# Wireach_internal_Buffered.net
KiCad netlist of a schematic drawn in EAGLE
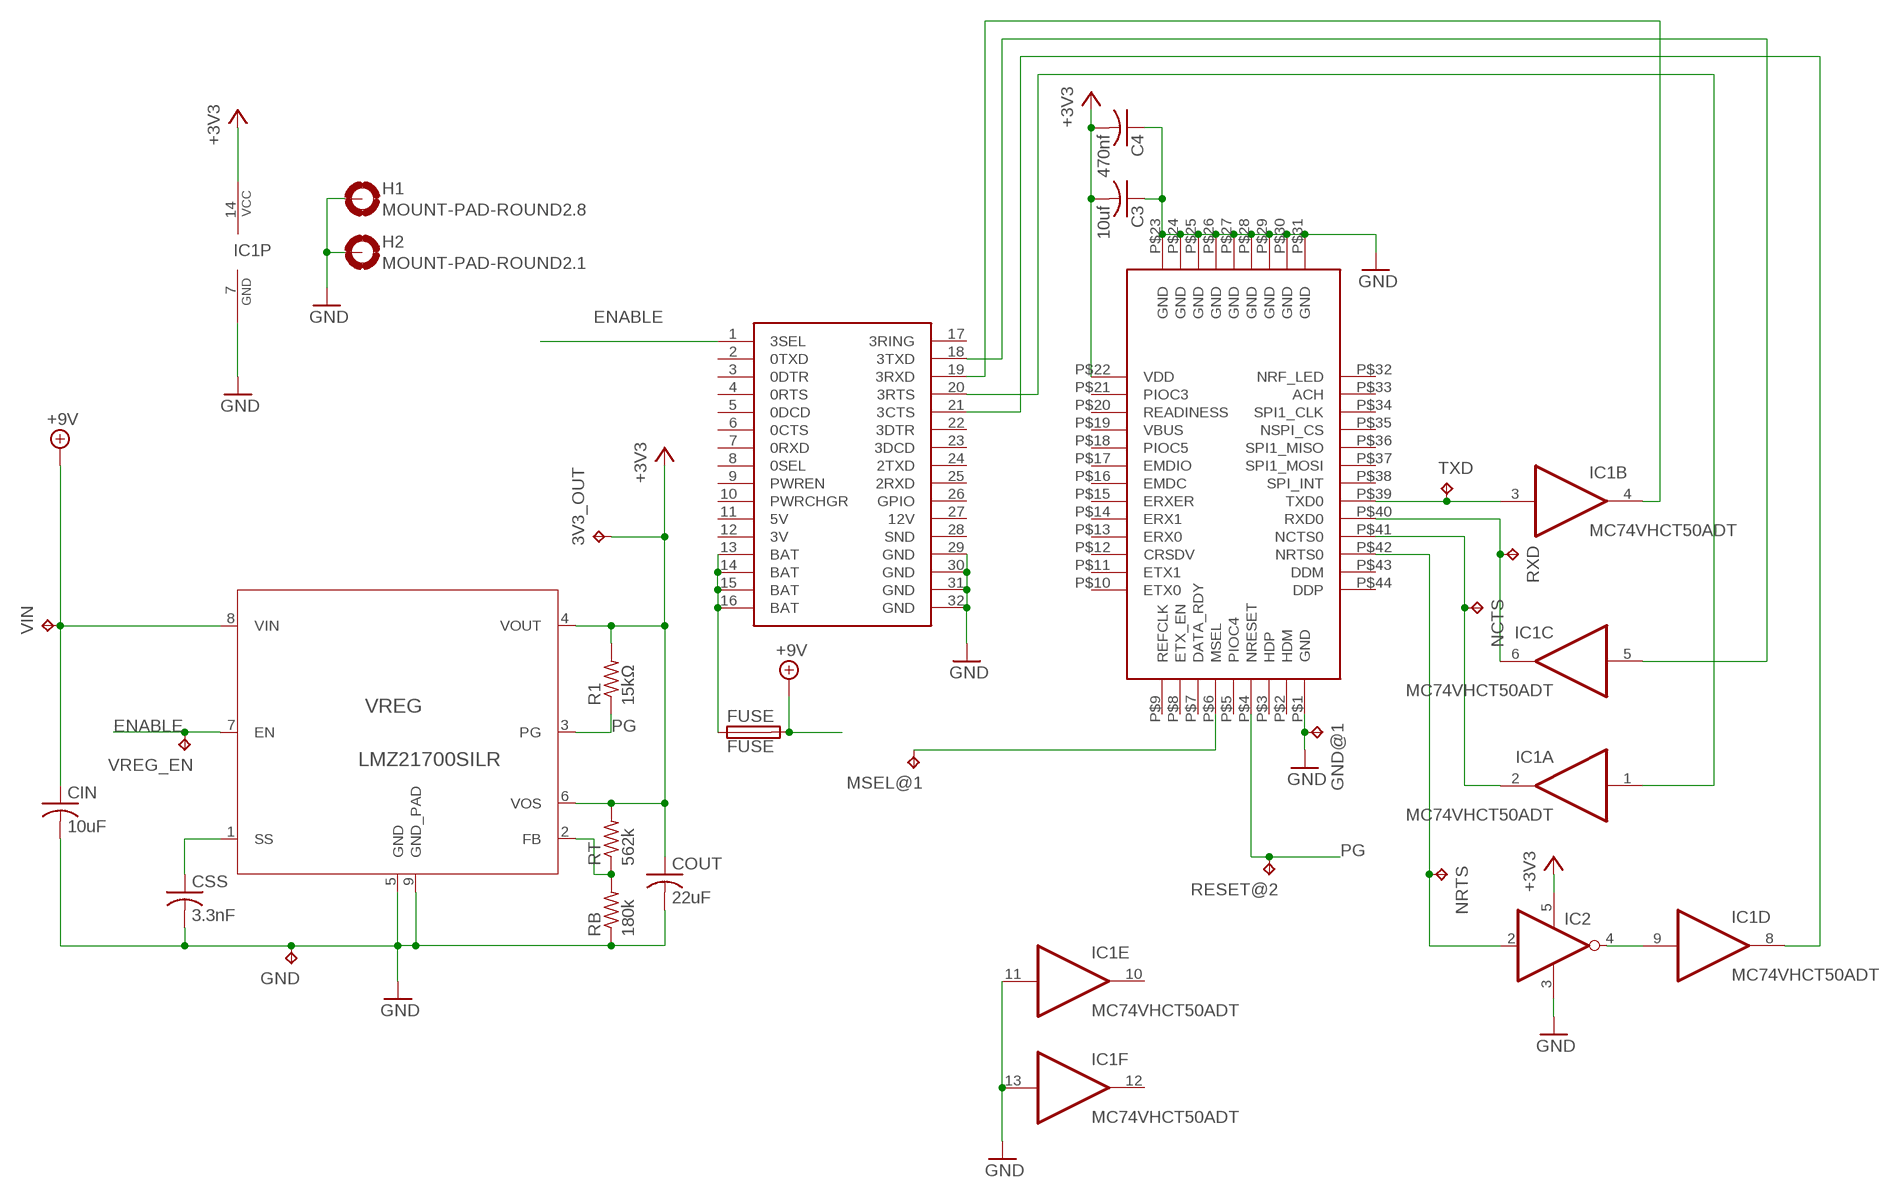
[diagram p0: schematic, sheet 1]

(export (version "E")
  (design (tool "Eeschema 10.0.6"))
  (components
    (comp (ref "3V3_OUT")
      (value "TPTP10R")
      (footprint "eagle-import:TP10R")
      (libsource (lib "eagle-import") (part "TPTP10R"))
    )
    (comp (ref "C3")
      (value "10uf")
      (footprint "eagle-import:C0805")
      (libsource (lib "eagle-import") (part "C-USC0805"))
    )
    (comp (ref "C4")
      (value "470nf")
      (footprint "eagle-import:C0805")
      (libsource (lib "eagle-import") (part "C-USC0805"))
    )
    (comp (ref "CIN")
      (value "10uF")
      (footprint "eagle-import:C0805K")
      (libsource (lib "eagle-import") (part "C-USC0805K"))
    )
    (comp (ref "COUT")
      (value "22uF")
      (footprint "eagle-import:C0805K")
      (libsource (lib "eagle-import") (part "C-USC0805K"))
    )
    (comp (ref "CSS")
      (value "3.3nF")
      (footprint "eagle-import:C0603K")
      (libsource (lib "eagle-import") (part "C-USC0603K"))
    )
    (comp (ref "FUSE")
      (value "FUSE")
      (footprint "eagle-import:R1206")
      (libsource (lib "eagle-import") (part "FUSE"))
    )
    (comp (ref "GND")
      (value "TPTP10R")
      (footprint "eagle-import:TP10R")
      (libsource (lib "eagle-import") (part "TPTP10R"))
    )
    (comp (ref "GND@1")
      (value "TPTP10R")
      (footprint "eagle-import:TP10R")
      (libsource (lib "eagle-import") (part "TPTP10R"))
    )
    (comp (ref "H1")
      (value "MOUNT-PAD-ROUND2.8")
      (footprint "eagle-import:2,8-PAD")
      (libsource (lib "eagle-import") (part "MOUNT-PAD-ROUND2.8"))
    )
    (comp (ref "H2")
      (value "MOUNT-PAD-ROUND2.1")
      (footprint "eagle-import:2,1-PAD")
      (libsource (lib "eagle-import") (part "MOUNT-PAD-ROUND2.1"))
    )
    (comp (ref "IC1")
      (value "MC74VHCT50ADT")
      (footprint "eagle-import:TSSOP14")
      (libsource (lib "eagle-import") (part "MC74VHCT50ADT"))
    )
    (comp (ref "IC2")
      (value "1G04-DC")
      (footprint "eagle-import:SOT353_5")
      (libsource (lib "eagle-import") (part "1G04-DC"))
    )
    (comp (ref "MSEL@1")
      (value "TPTP10R")
      (footprint "eagle-import:TP10R")
      (libsource (lib "eagle-import") (part "TPTP10R"))
    )
    (comp (ref "NCTS")
      (value "TPTP10R")
      (footprint "eagle-import:TP10R")
      (libsource (lib "eagle-import") (part "TPTP10R"))
    )
    (comp (ref "NRTS")
      (value "TPTP10R")
      (footprint "eagle-import:TP10R")
      (libsource (lib "eagle-import") (part "TPTP10R"))
    )
    (comp (ref "R1")
      (value "15kΩ")
      (footprint "eagle-import:R0603")
      (libsource (lib "eagle-import") (part "R-US_R0603"))
    )
    (comp (ref "RB")
      (value "180k")
      (footprint "eagle-import:R0603")
      (libsource (lib "eagle-import") (part "resistor_R-US_R0603"))
    )
    (comp (ref "RESET@2")
      (value "TPTP10R")
      (footprint "eagle-import:TP10R")
      (libsource (lib "eagle-import") (part "TPTP10R"))
    )
    (comp (ref "RT")
      (value "562k")
      (footprint "eagle-import:R0603")
      (libsource (lib "eagle-import") (part "resistor_R-US_R0603"))
    )
    (comp (ref "RXD")
      (value "TPTP10R")
      (footprint "eagle-import:TP10R")
      (libsource (lib "eagle-import") (part "TPTP10R"))
    )
    (comp (ref "TXD")
      (value "TPTP10R")
      (footprint "eagle-import:TP10R")
      (libsource (lib "eagle-import") (part "TPTP10R"))
    )
    (comp (ref "U$1")
      (value "WIREACH")
      (footprint "eagle-import:WIREACH")
      (libsource (lib "eagle-import") (part "WIREACH"))
    )
    (comp (ref "U$3")
      (value "N2-INTOLD")
      (footprint "eagle-import:NEWTON")
      (libsource (lib "eagle-import") (part "N2-INTOLD"))
    )
    (comp (ref "VIN")
      (value "TPTP10R")
      (footprint "eagle-import:TP10R")
      (libsource (lib "eagle-import") (part "TPTP10R"))
    )
    (comp (ref "VREG")
      (value "LMZ21700SILR")
      (footprint "eagle-import:SIL0008B")
      (libsource (lib "eagle-import") (part "LMZ21700SILR"))
    )
    (comp (ref "VREG_EN")
      (value "TPTP10R")
      (footprint "eagle-import:TP10R")
      (libsource (lib "eagle-import") (part "TPTP10R"))
    )
  )
  (nets
    (net (code "1") (name "+3V3") (class "Default")
      (node (ref "3V3_OUT") (pin "TP") (pinfunction "TP_TP") (pintype "input"))
      (node (ref "C3") (pin "2") (pinfunction "2_2") (pintype "passive"))
      (node (ref "C4") (pin "2") (pinfunction "2_2") (pintype "passive"))
      (node (ref "COUT") (pin "1") (pinfunction "1_1") (pintype "passive"))
      (node (ref "IC1") (pin "14") (pinfunction "VCC_14") (pintype "power_in"))
      (node (ref "IC2") (pin "5") (pinfunction "VDD_5") (pintype "power_in"))
      (node (ref "R1") (pin "2") (pinfunction "2_2") (pintype "passive"))
      (node (ref "RT") (pin "2") (pinfunction "2_2") (pintype "passive"))
      (node (ref "U$1") (pin "P$22") (pinfunction "VDD_P$22") (pintype "bidirectional"))
      (node (ref "VREG") (pin "4") (pinfunction "VOUT_4") (pintype "passive"))
      (node (ref "VREG") (pin "6") (pinfunction "VOS_6") (pintype "passive"))
    )
    (net (code "2") (name "+9V") (class "Default")
      (node (ref "CIN") (pin "1") (pinfunction "1_1") (pintype "passive"))
      (node (ref "FUSE") (pin "2") (pinfunction "2_2") (pintype "passive"))
      (node (ref "VIN") (pin "TP") (pinfunction "TP_TP") (pintype "input"))
      (node (ref "VREG") (pin "8") (pinfunction "VIN_8") (pintype "passive"))
    )
    (net (code "3") (name "/ENABLE") (class "Default")
      (node (ref "U$3") (pin "1") (pinfunction "3SEL_1") (pintype "bidirectional"))
      (node (ref "VREG") (pin "7") (pinfunction "EN_7") (pintype "passive"))
      (node (ref "VREG_EN") (pin "TP") (pinfunction "TP_TP") (pintype "input"))
    )
    (net (code "4") (name "/PG") (class "Default")
      (node (ref "R1") (pin "1") (pinfunction "1_1") (pintype "passive"))
      (node (ref "RESET@2") (pin "TP") (pinfunction "TP_TP") (pintype "input"))
      (node (ref "U$1") (pin "P$4") (pinfunction "NRESET_P$4") (pintype "bidirectional"))
      (node (ref "VREG") (pin "3") (pinfunction "PG_3") (pintype "passive"))
    )
    (net (code "5") (name "GND") (class "Default")
      (node (ref "C3") (pin "1") (pinfunction "1_1") (pintype "passive"))
      (node (ref "C4") (pin "1") (pinfunction "1_1") (pintype "passive"))
      (node (ref "CIN") (pin "2") (pinfunction "2_2") (pintype "passive"))
      (node (ref "COUT") (pin "2") (pinfunction "2_2") (pintype "passive"))
      (node (ref "CSS") (pin "2") (pinfunction "2_2") (pintype "passive"))
      (node (ref "GND") (pin "TP") (pinfunction "TP_TP") (pintype "input"))
      (node (ref "GND@1") (pin "TP") (pinfunction "TP_TP") (pintype "input"))
      (node (ref "H1") (pin "B2,8") (pinfunction "MOUNT_B2,8") (pintype "passive"))
      (node (ref "H2") (pin "B2,8") (pinfunction "MOUNT_B2,8") (pintype "passive"))
      (node (ref "IC1") (pin "11") (pinfunction "I_11") (pintype "input"))
      (node (ref "IC1") (pin "13") (pinfunction "I_13") (pintype "input"))
      (node (ref "IC1") (pin "7") (pinfunction "GND_7") (pintype "power_in"))
      (node (ref "IC2") (pin "3") (pinfunction "GND_3") (pintype "power_in"))
      (node (ref "RB") (pin "1") (pinfunction "1_1") (pintype "passive"))
      (node (ref "U$1") (pin "P$1") (pinfunction "GND_P$1") (pintype "bidirectional"))
      (node (ref "U$1") (pin "P$23") (pinfunction "GND_P$23") (pintype "bidirectional"))
      (node (ref "U$1") (pin "P$24") (pinfunction "GND_P$24") (pintype "bidirectional"))
      (node (ref "U$1") (pin "P$25") (pinfunction "GND_P$25") (pintype "bidirectional"))
      (node (ref "U$1") (pin "P$26") (pinfunction "GND_P$26") (pintype "bidirectional"))
      (node (ref "U$1") (pin "P$27") (pinfunction "GND_P$27") (pintype "bidirectional"))
      (node (ref "U$1") (pin "P$28") (pinfunction "GND_P$28") (pintype "bidirectional"))
      (node (ref "U$1") (pin "P$29") (pinfunction "GND_P$29") (pintype "bidirectional"))
      (node (ref "U$1") (pin "P$30") (pinfunction "GND_P$30") (pintype "bidirectional"))
      (node (ref "U$1") (pin "P$31") (pinfunction "GND_P$31") (pintype "bidirectional"))
      (node (ref "U$3") (pin "29") (pinfunction "GND_29") (pintype "bidirectional"))
      (node (ref "U$3") (pin "30") (pinfunction "GND_30") (pintype "bidirectional"))
      (node (ref "U$3") (pin "31") (pinfunction "GND_31") (pintype "bidirectional"))
      (node (ref "U$3") (pin "32") (pinfunction "GND_32") (pintype "bidirectional"))
      (node (ref "VREG") (pin "5") (pinfunction "GND_5") (pintype "passive"))
      (node (ref "VREG") (pin "9") (pinfunction "GND_PAD_9") (pintype "passive"))
    )
    (net (code "6") (name "Net-(FUSE-Pad1)") (class "Default")
      (node (ref "FUSE") (pin "1") (pinfunction "1_1") (pintype "passive"))
      (node (ref "U$3") (pin "13") (pinfunction "BAT_13") (pintype "bidirectional"))
      (node (ref "U$3") (pin "14") (pinfunction "BAT_14") (pintype "bidirectional"))
      (node (ref "U$3") (pin "15") (pinfunction "BAT_15") (pintype "bidirectional"))
      (node (ref "U$3") (pin "16") (pinfunction "BAT_16") (pintype "bidirectional"))
    )
    (net (code "7") (name "Net-(IC1A-I)") (class "Default")
      (node (ref "IC1") (pin "1") (pinfunction "I_1") (pintype "input"))
      (node (ref "U$3") (pin "20") (pinfunction "3RTS_20") (pintype "bidirectional"))
    )
    (net (code "8") (name "Net-(IC1A-O)") (class "Default")
      (node (ref "IC1") (pin "2") (pinfunction "O_2") (pintype "open_collector"))
      (node (ref "NCTS") (pin "TP") (pinfunction "TP_TP") (pintype "input"))
      (node (ref "U$1") (pin "P$41") (pinfunction "NCTS0_P$41") (pintype "bidirectional"))
    )
    (net (code "9") (name "Net-(IC1B-I)") (class "Default")
      (node (ref "IC1") (pin "3") (pinfunction "I_3") (pintype "input"))
      (node (ref "TXD") (pin "TP") (pinfunction "TP_TP") (pintype "input"))
      (node (ref "U$1") (pin "P$39") (pinfunction "TXD0_P$39") (pintype "bidirectional"))
    )
    (net (code "10") (name "Net-(IC1B-O)") (class "Default")
      (node (ref "IC1") (pin "4") (pinfunction "O_4") (pintype "open_collector"))
      (node (ref "U$3") (pin "19") (pinfunction "3RXD_19") (pintype "bidirectional"))
    )
    (net (code "11") (name "Net-(IC1C-I)") (class "Default")
      (node (ref "IC1") (pin "5") (pinfunction "I_5") (pintype "input"))
      (node (ref "U$3") (pin "18") (pinfunction "3TXD_18") (pintype "bidirectional"))
    )
    (net (code "12") (name "Net-(IC1C-O)") (class "Default")
      (node (ref "IC1") (pin "6") (pinfunction "O_6") (pintype "open_collector"))
      (node (ref "RXD") (pin "TP") (pinfunction "TP_TP") (pintype "input"))
      (node (ref "U$1") (pin "P$40") (pinfunction "RXD0_P$40") (pintype "bidirectional"))
    )
    (net (code "13") (name "Net-(IC1D-I)") (class "Default")
      (node (ref "IC1") (pin "9") (pinfunction "I_9") (pintype "input"))
      (node (ref "IC2") (pin "4") (pinfunction "O_4") (pintype "output"))
    )
    (net (code "14") (name "Net-(IC1D-O)") (class "Default")
      (node (ref "IC1") (pin "8") (pinfunction "O_8") (pintype "open_collector"))
      (node (ref "U$3") (pin "21") (pinfunction "3CTS_21") (pintype "bidirectional"))
    )
    (net (code "15") (name "Net-(IC2-I)") (class "Default")
      (node (ref "IC2") (pin "2") (pinfunction "I_2") (pintype "input"))
      (node (ref "NRTS") (pin "TP") (pinfunction "TP_TP") (pintype "input"))
      (node (ref "U$1") (pin "P$42") (pinfunction "NRTS0_P$42") (pintype "bidirectional"))
    )
    (net (code "16") (name "Net-(U$1-MSEL)") (class "Default")
      (node (ref "MSEL@1") (pin "TP") (pinfunction "TP_TP") (pintype "input"))
      (node (ref "U$1") (pin "P$6") (pinfunction "MSEL_P$6") (pintype "bidirectional"))
    )
    (net (code "17") (name "Net-(VREG-FB)") (class "Default")
      (node (ref "RB") (pin "2") (pinfunction "2_2") (pintype "passive"))
      (node (ref "RT") (pin "1") (pinfunction "1_1") (pintype "passive"))
      (node (ref "VREG") (pin "2") (pinfunction "FB_2") (pintype "passive"))
    )
    (net (code "18") (name "Net-(VREG-SS)") (class "Default")
      (node (ref "CSS") (pin "1") (pinfunction "1_1") (pintype "passive"))
      (node (ref "VREG") (pin "1") (pinfunction "SS_1") (pintype "passive"))
    )
    (net (code "19") (name "unconnected-(IC1E-O-Pad10)") (class "Default")
      (node (ref "IC1") (pin "10") (pinfunction "O_10") (pintype "open_collector"))
    )
    (net (code "20") (name "unconnected-(IC1F-O-Pad12)") (class "Default")
      (node (ref "IC1") (pin "12") (pinfunction "O_12") (pintype "open_collector"))
    )
    (net (code "21") (name "unconnected-(U$1-ACH-PadP$33)") (class "Default")
      (node (ref "U$1") (pin "P$33") (pinfunction "ACH_P$33") (pintype "bidirectional"))
    )
    (net (code "22") (name "unconnected-(U$1-CRSDV-PadP$12)") (class "Default")
      (node (ref "U$1") (pin "P$12") (pinfunction "CRSDV_P$12") (pintype "bidirectional"))
    )
    (net (code "23") (name "unconnected-(U$1-DATA_RDY-PadP$7)") (class "Default")
      (node (ref "U$1") (pin "P$7") (pinfunction "DATA_RDY_P$7") (pintype "bidirectional"))
    )
    (net (code "24") (name "unconnected-(U$1-DDM-PadP$43)") (class "Default")
      (node (ref "U$1") (pin "P$43") (pinfunction "DDM_P$43") (pintype "bidirectional"))
    )
    (net (code "25") (name "unconnected-(U$1-DDP-PadP$44)") (class "Default")
      (node (ref "U$1") (pin "P$44") (pinfunction "DDP_P$44") (pintype "bidirectional"))
    )
    (net (code "26") (name "unconnected-(U$1-EMDC-PadP$16)") (class "Default")
      (node (ref "U$1") (pin "P$16") (pinfunction "EMDC_P$16") (pintype "bidirectional"))
    )
    (net (code "27") (name "unconnected-(U$1-EMDIO-PadP$17)") (class "Default")
      (node (ref "U$1") (pin "P$17") (pinfunction "EMDIO_P$17") (pintype "bidirectional"))
    )
    (net (code "28") (name "unconnected-(U$1-ERX0-PadP$13)") (class "Default")
      (node (ref "U$1") (pin "P$13") (pinfunction "ERX0_P$13") (pintype "bidirectional"))
    )
    (net (code "29") (name "unconnected-(U$1-ERX1-PadP$14)") (class "Default")
      (node (ref "U$1") (pin "P$14") (pinfunction "ERX1_P$14") (pintype "bidirectional"))
    )
    (net (code "30") (name "unconnected-(U$1-ERXER-PadP$15)") (class "Default")
      (node (ref "U$1") (pin "P$15") (pinfunction "ERXER_P$15") (pintype "bidirectional"))
    )
    (net (code "31") (name "unconnected-(U$1-ETX0-PadP$10)") (class "Default")
      (node (ref "U$1") (pin "P$10") (pinfunction "ETX0_P$10") (pintype "bidirectional"))
    )
    (net (code "32") (name "unconnected-(U$1-ETX1-PadP$11)") (class "Default")
      (node (ref "U$1") (pin "P$11") (pinfunction "ETX1_P$11") (pintype "bidirectional"))
    )
    (net (code "33") (name "unconnected-(U$1-ETX_EN-PadP$8)") (class "Default")
      (node (ref "U$1") (pin "P$8") (pinfunction "ETX_EN_P$8") (pintype "bidirectional"))
    )
    (net (code "34") (name "unconnected-(U$1-HDM-PadP$2)") (class "Default")
      (node (ref "U$1") (pin "P$2") (pinfunction "HDM_P$2") (pintype "bidirectional"))
    )
    (net (code "35") (name "unconnected-(U$1-HDP-PadP$3)") (class "Default")
      (node (ref "U$1") (pin "P$3") (pinfunction "HDP_P$3") (pintype "bidirectional"))
    )
    (net (code "36") (name "unconnected-(U$1-NRF_LED-PadP$32)") (class "Default")
      (node (ref "U$1") (pin "P$32") (pinfunction "NRF_LED_P$32") (pintype "bidirectional"))
    )
    (net (code "37") (name "unconnected-(U$1-NSPI_CS-PadP$35)") (class "Default")
      (node (ref "U$1") (pin "P$35") (pinfunction "NSPI_CS_P$35") (pintype "bidirectional"))
    )
    (net (code "38") (name "unconnected-(U$1-PIOC3-PadP$21)") (class "Default")
      (node (ref "U$1") (pin "P$21") (pinfunction "PIOC3_P$21") (pintype "bidirectional"))
    )
    (net (code "39") (name "unconnected-(U$1-PIOC4-PadP$5)") (class "Default")
      (node (ref "U$1") (pin "P$5") (pinfunction "PIOC4_P$5") (pintype "bidirectional"))
    )
    (net (code "40") (name "unconnected-(U$1-PIOC5-PadP$18)") (class "Default")
      (node (ref "U$1") (pin "P$18") (pinfunction "PIOC5_P$18") (pintype "bidirectional"))
    )
    (net (code "41") (name "unconnected-(U$1-READINESS-PadP$20)") (class "Default")
      (node (ref "U$1") (pin "P$20") (pinfunction "READINESS_P$20") (pintype "bidirectional"))
    )
    (net (code "42") (name "unconnected-(U$1-REFCLK-PadP$9)") (class "Default")
      (node (ref "U$1") (pin "P$9") (pinfunction "REFCLK_P$9") (pintype "bidirectional"))
    )
    (net (code "43") (name "unconnected-(U$1-SPI1_CLK-PadP$34)") (class "Default")
      (node (ref "U$1") (pin "P$34") (pinfunction "SPI1_CLK_P$34") (pintype "bidirectional"))
    )
    (net (code "44") (name "unconnected-(U$1-SPI1_MISO-PadP$36)") (class "Default")
      (node (ref "U$1") (pin "P$36") (pinfunction "SPI1_MISO_P$36") (pintype "bidirectional"))
    )
    (net (code "45") (name "unconnected-(U$1-SPI1_MOSI-PadP$37)") (class "Default")
      (node (ref "U$1") (pin "P$37") (pinfunction "SPI1_MOSI_P$37") (pintype "bidirectional"))
    )
    (net (code "46") (name "unconnected-(U$1-SPI_INT-PadP$38)") (class "Default")
      (node (ref "U$1") (pin "P$38") (pinfunction "SPI_INT_P$38") (pintype "bidirectional"))
    )
    (net (code "47") (name "unconnected-(U$1-VBUS-PadP$19)") (class "Default")
      (node (ref "U$1") (pin "P$19") (pinfunction "VBUS_P$19") (pintype "bidirectional"))
    )
    (net (code "48") (name "unconnected-(U$3-0CTS-Pad6)") (class "Default")
      (node (ref "U$3") (pin "6") (pinfunction "0CTS_6") (pintype "bidirectional"))
    )
    (net (code "49") (name "unconnected-(U$3-0DCD-Pad5)") (class "Default")
      (node (ref "U$3") (pin "5") (pinfunction "0DCD_5") (pintype "bidirectional"))
    )
    (net (code "50") (name "unconnected-(U$3-0DTR-Pad3)") (class "Default")
      (node (ref "U$3") (pin "3") (pinfunction "0DTR_3") (pintype "bidirectional"))
    )
    (net (code "51") (name "unconnected-(U$3-0RTS-Pad4)") (class "Default")
      (node (ref "U$3") (pin "4") (pinfunction "0RTS_4") (pintype "bidirectional"))
    )
    (net (code "52") (name "unconnected-(U$3-0RXD-Pad7)") (class "Default")
      (node (ref "U$3") (pin "7") (pinfunction "0RXD_7") (pintype "bidirectional"))
    )
    (net (code "53") (name "unconnected-(U$3-0SEL-Pad8)") (class "Default")
      (node (ref "U$3") (pin "8") (pinfunction "0SEL_8") (pintype "bidirectional"))
    )
    (net (code "54") (name "unconnected-(U$3-0TXD-Pad2)") (class "Default")
      (node (ref "U$3") (pin "2") (pinfunction "0TXD_2") (pintype "bidirectional"))
    )
    (net (code "55") (name "unconnected-(U$3-2RXD-Pad25)") (class "Default")
      (node (ref "U$3") (pin "25") (pinfunction "2RXD_25") (pintype "bidirectional"))
    )
    (net (code "56") (name "unconnected-(U$3-2TXD-Pad24)") (class "Default")
      (node (ref "U$3") (pin "24") (pinfunction "2TXD_24") (pintype "bidirectional"))
    )
    (net (code "57") (name "unconnected-(U$3-3DCD-Pad23)") (class "Default")
      (node (ref "U$3") (pin "23") (pinfunction "3DCD_23") (pintype "bidirectional"))
    )
    (net (code "58") (name "unconnected-(U$3-3DTR-Pad22)") (class "Default")
      (node (ref "U$3") (pin "22") (pinfunction "3DTR_22") (pintype "bidirectional"))
    )
    (net (code "59") (name "unconnected-(U$3-3RING-Pad17)") (class "Default")
      (node (ref "U$3") (pin "17") (pinfunction "3RING_17") (pintype "bidirectional"))
    )
    (net (code "60") (name "unconnected-(U$3-3V-Pad12)") (class "Default")
      (node (ref "U$3") (pin "12") (pinfunction "3V_12") (pintype "bidirectional"))
    )
    (net (code "61") (name "unconnected-(U$3-5V-Pad11)") (class "Default")
      (node (ref "U$3") (pin "11") (pinfunction "5V_11") (pintype "bidirectional"))
    )
    (net (code "62") (name "unconnected-(U$3-12V-Pad27)") (class "Default")
      (node (ref "U$3") (pin "27") (pinfunction "12V_27") (pintype "bidirectional"))
    )
    (net (code "63") (name "unconnected-(U$3-GPIO-Pad26)") (class "Default")
      (node (ref "U$3") (pin "26") (pinfunction "GPIO_26") (pintype "bidirectional"))
    )
    (net (code "64") (name "unconnected-(U$3-PWRCHGR-Pad10)") (class "Default")
      (node (ref "U$3") (pin "10") (pinfunction "PWRCHGR_10") (pintype "bidirectional"))
    )
    (net (code "65") (name "unconnected-(U$3-PWREN-Pad9)") (class "Default")
      (node (ref "U$3") (pin "9") (pinfunction "PWREN_9") (pintype "bidirectional"))
    )
    (net (code "66") (name "unconnected-(U$3-SND-Pad28)") (class "Default")
      (node (ref "U$3") (pin "28") (pinfunction "SND_28") (pintype "bidirectional"))
    )
  )
)
